# NFC.net
KiCad netlist of a schematic drawn in Altium Designer
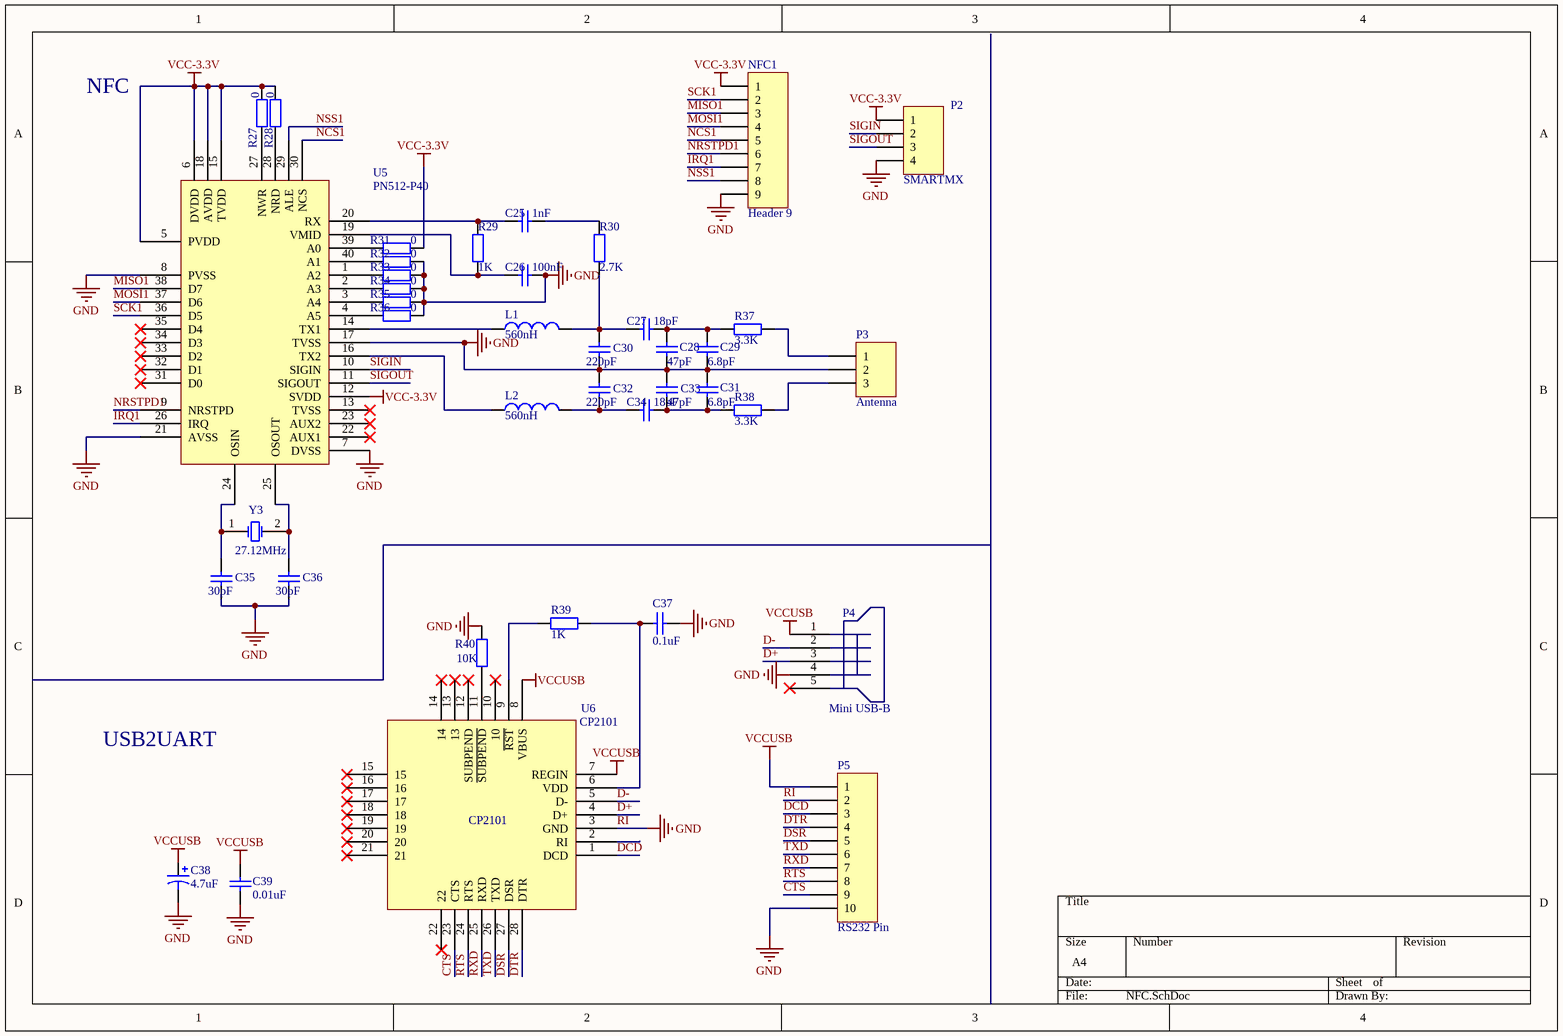
[diagram p0: NFC.SchDoc]

(export (version "E")
  (design (tool "Eeschema 10.0.6"))
  (components
    (comp (ref "C25")
      (value "1nF")
      (footprint "1608[0603]")
      (description "Capacitor")
      (fields (field (name "Comment") "Cap") (field (name "PUBLISHER") "Altium Limited"))
      (libsource (lib "common") (part "Cap"))
    )
    (comp (ref "C26")
      (value "100nF")
      (footprint "1608[0603]")
      (description "Capacitor")
      (fields (field (name "Comment") "Cap") (field (name "PUBLISHER") "Altium Limited"))
      (libsource (lib "common") (part "Cap"))
    )
    (comp (ref "C27")
      (value "18pF")
      (footprint "1608[0603]")
      (description "Capacitor")
      (fields (field (name "Comment") "Cap") (field (name "PUBLISHER") "Altium Limited"))
      (libsource (lib "common") (part "Cap"))
    )
    (comp (ref "C28")
      (value "47pF")
      (footprint "1608[0603]")
      (description "Capacitor")
      (fields (field (name "Comment") "Cap") (field (name "PUBLISHER") "Altium Limited"))
      (libsource (lib "common") (part "Cap"))
    )
    (comp (ref "C29")
      (value "6.8pF")
      (footprint "1608[0603]")
      (description "Capacitor")
      (fields (field (name "Comment") "Cap") (field (name "PUBLISHER") "Altium Limited"))
      (libsource (lib "common") (part "Cap"))
    )
    (comp (ref "C30")
      (value "220pF")
      (footprint "1608[0603]")
      (description "Capacitor")
      (fields (field (name "Comment") "Cap") (field (name "PUBLISHER") "Altium Limited"))
      (libsource (lib "common") (part "Cap"))
    )
    (comp (ref "C31")
      (value "6.8pF")
      (footprint "1608[0603]")
      (description "Capacitor")
      (fields (field (name "Comment") "Cap") (field (name "PUBLISHER") "Altium Limited"))
      (libsource (lib "common") (part "Cap"))
    )
    (comp (ref "C32")
      (value "220pF")
      (footprint "1608[0603]")
      (description "Capacitor")
      (fields (field (name "Comment") "Cap") (field (name "PUBLISHER") "Altium Limited"))
      (libsource (lib "common") (part "Cap"))
    )
    (comp (ref "C33")
      (value "47pF")
      (footprint "1608[0603]")
      (description "Capacitor")
      (fields (field (name "Comment") "Cap") (field (name "PUBLISHER") "Altium Limited"))
      (libsource (lib "common") (part "Cap"))
    )
    (comp (ref "C34")
      (value "18pF")
      (footprint "1608[0603]")
      (description "Capacitor")
      (fields (field (name "Comment") "Cap") (field (name "PUBLISHER") "Altium Limited"))
      (libsource (lib "common") (part "Cap"))
    )
    (comp (ref "C35")
      (value "30pF")
      (footprint "1608[0603]")
      (description "Capacitor")
      (fields (field (name "Comment") "Cap") (field (name "PUBLISHER") "Altium Limited"))
      (libsource (lib "common") (part "Cap"))
    )
    (comp (ref "C36")
      (value "30pF")
      (footprint "1608[0603]")
      (description "Capacitor")
      (fields (field (name "Comment") "Cap") (field (name "PUBLISHER") "Altium Limited"))
      (libsource (lib "common") (part "Cap"))
    )
    (comp (ref "C37")
      (value "0.1uF")
      (footprint "1608[0603]")
      (description "Capacitor")
      (fields (field (name "Comment") "Cap") (field (name "PUBLISHER") "Altium Limited"))
      (libsource (lib "common") (part "Cap"))
    )
    (comp (ref "C38")
      (value "4.7uF")
      (footprint "2012[0805] - POL")
      (description "Polarized Capacitor (Axial)")
      (fields (field (name "Comment") "CAP POL") (field (name "PUBLISHER") "Altium Limited"))
      (libsource (lib "common") (part "CAP POL"))
    )
    (comp (ref "C39")
      (value "0.01uF")
      (footprint "1608[0603]")
      (description "Capacitor")
      (fields (field (name "Comment") "Cap") (field (name "PUBLISHER") "Altium Limited"))
      (libsource (lib "common") (part "Cap"))
    )
    (comp (ref "L1")
      (value "560nH")
      (footprint "0402-A")
      (description "Inductor")
      (fields (field (name "PUBLISHER") "Altium Limited"))
      (libsource (lib "Miscellaneous Devices") (part "Inductor"))
    )
    (comp (ref "L2")
      (value "560nH")
      (footprint "0402-A")
      (description "Inductor")
      (fields (field (name "PUBLISHER") "Altium Limited"))
      (libsource (lib "Miscellaneous Devices") (part "Inductor"))
    )
    (comp (ref "NFC1")
      (value "Header 9")
      (footprint "HDR1X9")
      (description "Header, 9-Pin")
      (fields (field (name "PUBLISHER") "Altium Limited"))
      (libsource (lib "Miscellaneous Connectors") (part "Header 9"))
    )
    (comp (ref "P2")
      (value "SMARTMX")
      (footprint "HDR1X4")
      (description "Header, 4-Pin")
      (fields (field (name "PUBLISHER") "Altium Limited"))
      (libsource (lib "Miscellaneous Connectors") (part "Header 4"))
    )
    (comp (ref "P3")
      (value "Antenna")
      (footprint "HDR1X3")
      (description "Header, 3-Pin")
      (fields (field (name "PUBLISHER") "Altium Limited"))
      (libsource (lib "Miscellaneous Connectors") (part "Header 3"))
    )
    (comp (ref "P4")
      (value "Mini USB-B")
      (footprint "MINI USB-501")
      (description "Mini USB Type B")
      (libsource (lib "USB2UART") (part "USB"))
    )
    (comp (ref "P5")
      (value "RS232 Pin")
      (footprint "HDR1X10")
      (description "Header, 10-Pin")
      (fields (field (name "PUBLISHER") "Altium Limited"))
      (libsource (lib "Miscellaneous Connectors") (part "Header 10"))
    )
    (comp (ref "R27")
      (value "0")
      (footprint "1608[0603]")
      (description "Resistor")
      (fields (field (name "Comment") "RES") (field (name "PUBLISHER") "Altium Limited"))
      (libsource (lib "") (part "RES_1"))
    )
    (comp (ref "R28")
      (value "0")
      (footprint "1608[0603]")
      (description "Resistor")
      (fields (field (name "Comment") "RES") (field (name "PUBLISHER") "Altium Limited"))
      (libsource (lib "") (part "RES_1"))
    )
    (comp (ref "R29")
      (value "1K")
      (footprint "1608[0603]")
      (description "Resistor")
      (fields (field (name "Comment") "RES") (field (name "PUBLISHER") "Altium Limited"))
      (libsource (lib "") (part "RES_1"))
    )
    (comp (ref "R30")
      (value "2.7K")
      (footprint "1608[0603]")
      (description "Resistor")
      (fields (field (name "Comment") "RES") (field (name "PUBLISHER") "Altium Limited"))
      (libsource (lib "") (part "RES_1"))
    )
    (comp (ref "R31")
      (value "0")
      (footprint "1608[0603]")
      (description "Resistor")
      (fields (field (name "Comment") "RES") (field (name "PUBLISHER") "Altium Limited"))
      (libsource (lib "common") (part "RES"))
    )
    (comp (ref "R32")
      (value "0")
      (footprint "1608[0603]")
      (description "Resistor")
      (fields (field (name "Comment") "RES") (field (name "PUBLISHER") "Altium Limited"))
      (libsource (lib "common") (part "RES"))
    )
    (comp (ref "R33")
      (value "0")
      (footprint "1608[0603]")
      (description "Resistor")
      (fields (field (name "Comment") "RES") (field (name "PUBLISHER") "Altium Limited"))
      (libsource (lib "common") (part "RES"))
    )
    (comp (ref "R34")
      (value "0")
      (footprint "1608[0603]")
      (description "Resistor")
      (fields (field (name "Comment") "RES") (field (name "PUBLISHER") "Altium Limited"))
      (libsource (lib "common") (part "RES"))
    )
    (comp (ref "R35")
      (value "0")
      (footprint "1608[0603]")
      (description "Resistor")
      (fields (field (name "Comment") "RES") (field (name "PUBLISHER") "Altium Limited"))
      (libsource (lib "common") (part "RES"))
    )
    (comp (ref "R36")
      (value "0")
      (footprint "1608[0603]")
      (description "Resistor")
      (fields (field (name "Comment") "RES") (field (name "PUBLISHER") "Altium Limited"))
      (libsource (lib "common") (part "RES"))
    )
    (comp (ref "R37")
      (value "3.3K")
      (footprint "1608[0603]")
      (description "Resistor")
      (fields (field (name "Comment") "RES") (field (name "PUBLISHER") "Altium Limited"))
      (libsource (lib "common") (part "RES"))
    )
    (comp (ref "R38")
      (value "3.3K")
      (footprint "1608[0603]")
      (description "Resistor")
      (fields (field (name "Comment") "RES") (field (name "PUBLISHER") "Altium Limited"))
      (libsource (lib "common") (part "RES"))
    )
    (comp (ref "R39")
      (value "1K")
      (footprint "1608[0603]")
      (description "Resistor")
      (fields (field (name "Comment") "Res") (field (name "PUBLISHER") "Altium Limited"))
      (libsource (lib "common") (part "RES"))
    )
    (comp (ref "R40")
      (value "10K")
      (footprint "1608[0603]")
      (description "Resistor")
      (fields (field (name "Comment") "Res") (field (name "PUBLISHER") "Altium Limited"))
      (libsource (lib "") (part "RES_1"))
    )
    (comp (ref "U5")
      (value "PN512-P40")
      (footprint "QFN50P600X600-40VN")
      (libsource (lib "*") (part "PN511-P40"))
    )
    (comp (ref "U6")
      (value "CP2101")
      (footprint "QFN50P500X500-28VAN")
      (libsource (lib "USB2UART") (part "CP2101"))
    )
    (comp (ref "Y3")
      (value "27.12MHz")
      (footprint "XTAL")
      (description "Crystal Oscillator")
      (fields (field (name "PUBLISHER") "Altium Limited"))
      (libsource (lib "common") (part "XTAL"))
    )
  )
  (nets
    (net (code "1") (name "/CTS") (class "Default")
      (node (ref "P5") (pin "9") (pinfunction "9_9") (pintype "passive"))
      (node (ref "U6") (pin "23") (pinfunction "CTS_23") (pintype "passive"))
    )
    (net (code "2") (name "/D+") (class "Default")
      (node (ref "P4") (pin "3") (pinfunction "3_3") (pintype "passive"))
      (node (ref "U6") (pin "4") (pinfunction "D+_4") (pintype "passive"))
    )
    (net (code "3") (name "/D-") (class "Default")
      (node (ref "P4") (pin "2") (pinfunction "2_2") (pintype "passive"))
      (node (ref "U6") (pin "5") (pinfunction "D-_5") (pintype "passive"))
    )
    (net (code "4") (name "/DCD") (class "Default")
      (node (ref "P5") (pin "3") (pinfunction "3_3") (pintype "passive"))
      (node (ref "U6") (pin "1") (pinfunction "DCD_1") (pintype "passive"))
    )
    (net (code "5") (name "/DSR") (class "Default")
      (node (ref "P5") (pin "5") (pinfunction "5_5") (pintype "passive"))
      (node (ref "U6") (pin "27") (pinfunction "DSR_27") (pintype "passive"))
    )
    (net (code "6") (name "/DTR") (class "Default")
      (node (ref "P5") (pin "4") (pinfunction "4_4") (pintype "passive"))
      (node (ref "U6") (pin "28") (pinfunction "DTR_28") (pintype "passive"))
    )
    (net (code "7") (name "/IRQ1") (class "Default")
      (node (ref "NFC1") (pin "7") (pinfunction "7_7") (pintype "passive"))
      (node (ref "U5") (pin "26") (pinfunction "IRQ_26") (pintype "passive"))
    )
    (net (code "8") (name "/MISO1") (class "Default")
      (node (ref "NFC1") (pin "3") (pinfunction "3_3") (pintype "passive"))
      (node (ref "U5") (pin "38") (pinfunction "D7_38") (pintype "passive"))
    )
    (net (code "9") (name "/MOSI1") (class "Default")
      (node (ref "NFC1") (pin "4") (pinfunction "4_4") (pintype "passive"))
      (node (ref "U5") (pin "37") (pinfunction "D6_37") (pintype "passive"))
    )
    (net (code "10") (name "/NCS1") (class "Default")
      (node (ref "NFC1") (pin "5") (pinfunction "5_5") (pintype "passive"))
      (node (ref "U5") (pin "30") (pinfunction "NCS_30") (pintype "passive"))
    )
    (net (code "11") (name "/NRSTPD1") (class "Default")
      (node (ref "NFC1") (pin "6") (pinfunction "6_6") (pintype "passive"))
      (node (ref "U5") (pin "9") (pinfunction "NRSTPD_9") (pintype "passive"))
    )
    (net (code "12") (name "/NSS1") (class "Default")
      (node (ref "NFC1") (pin "8") (pinfunction "8_8") (pintype "passive"))
      (node (ref "U5") (pin "29") (pinfunction "ALE_29") (pintype "passive"))
    )
    (net (code "13") (name "/RTS") (class "Default")
      (node (ref "P5") (pin "8") (pinfunction "8_8") (pintype "passive"))
      (node (ref "U6") (pin "24") (pinfunction "RTS_24") (pintype "passive"))
    )
    (net (code "14") (name "/RXD") (class "Default")
      (node (ref "P5") (pin "7") (pinfunction "7_7") (pintype "passive"))
      (node (ref "U6") (pin "25") (pinfunction "RXD_25") (pintype "passive"))
    )
    (net (code "15") (name "/SCK1") (class "Default")
      (node (ref "NFC1") (pin "2") (pinfunction "2_2") (pintype "passive"))
      (node (ref "U5") (pin "36") (pinfunction "D5_36") (pintype "passive"))
    )
    (net (code "16") (name "/SIGIN") (class "Default")
      (node (ref "P2") (pin "2") (pinfunction "2_2") (pintype "passive"))
      (node (ref "U5") (pin "10") (pinfunction "SIGIN_10") (pintype "passive"))
    )
    (net (code "17") (name "/SIGOUT") (class "Default")
      (node (ref "P2") (pin "3") (pinfunction "3_3") (pintype "passive"))
      (node (ref "U5") (pin "11") (pinfunction "SIGOUT_11") (pintype "passive"))
    )
    (net (code "18") (name "/TXD") (class "Default")
      (node (ref "P5") (pin "6") (pinfunction "6_6") (pintype "passive"))
      (node (ref "U6") (pin "26") (pinfunction "TXD_26") (pintype "passive"))
    )
    (net (code "19") (name "GND") (class "Default")
      (node (ref "C26") (pin "2") (pinfunction "2_2") (pintype "passive"))
      (node (ref "C28") (pin "1") (pinfunction "1_1") (pintype "passive"))
      (node (ref "C29") (pin "1") (pinfunction "1_1") (pintype "passive"))
      (node (ref "C30") (pin "1") (pinfunction "1_1") (pintype "passive"))
      (node (ref "C31") (pin "2") (pinfunction "2_2") (pintype "passive"))
      (node (ref "C32") (pin "2") (pinfunction "2_2") (pintype "passive"))
      (node (ref "C33") (pin "2") (pinfunction "2_2") (pintype "passive"))
      (node (ref "C35") (pin "1") (pinfunction "1_1") (pintype "passive"))
      (node (ref "C36") (pin "1") (pinfunction "1_1") (pintype "passive"))
      (node (ref "C37") (pin "1") (pinfunction "1_1") (pintype "passive"))
      (node (ref "C38") (pin "2") (pinfunction "2_2") (pintype "passive"))
      (node (ref "C39") (pin "1") (pinfunction "1_1") (pintype "passive"))
      (node (ref "NFC1") (pin "9") (pinfunction "9_9") (pintype "passive"))
      (node (ref "P2") (pin "4") (pinfunction "4_4") (pintype "passive"))
      (node (ref "P3") (pin "2") (pinfunction "2_2") (pintype "passive"))
      (node (ref "P4") (pin "4") (pinfunction "4_4") (pintype "passive"))
      (node (ref "P5") (pin "10") (pinfunction "10_10") (pintype "passive"))
      (node (ref "P5") (pin "2") (pinfunction "2_2") (pintype "passive"))
      (node (ref "R32") (pin "1") (pinfunction "1_1") (pintype "passive"))
      (node (ref "R33") (pin "1") (pinfunction "1_1") (pintype "passive"))
      (node (ref "R34") (pin "1") (pinfunction "1_1") (pintype "passive"))
      (node (ref "R35") (pin "1") (pinfunction "1_1") (pintype "passive"))
      (node (ref "R36") (pin "1") (pinfunction "1_1") (pintype "passive"))
      (node (ref "R40") (pin "2") (pinfunction "2_2") (pintype "passive"))
      (node (ref "U5") (pin "17") (pinfunction "TVSS_17") (pintype "passive"))
      (node (ref "U5") (pin "21") (pinfunction "AVSS_21") (pintype "passive"))
      (node (ref "U5") (pin "7") (pinfunction "DVSS_7") (pintype "passive"))
      (node (ref "U5") (pin "8") (pinfunction "PVSS_8") (pintype "passive"))
      (node (ref "U6") (pin "3") (pinfunction "GND_3") (pintype "passive"))
    )
    (net (code "20") (name "Net-(C25-Pad2)") (class "Default")
      (node (ref "C25") (pin "2") (pinfunction "2_2") (pintype "passive"))
      (node (ref "R30") (pin "2") (pinfunction "2_2") (pintype "passive"))
    )
    (net (code "21") (name "Net-(C27-Pad1)") (class "Default")
      (node (ref "C27") (pin "1") (pinfunction "1_1") (pintype "passive"))
      (node (ref "C30") (pin "2") (pinfunction "2_2") (pintype "passive"))
      (node (ref "L1") (pin "2") (pinfunction "2_2") (pintype "passive"))
      (node (ref "R30") (pin "1") (pinfunction "1_1") (pintype "passive"))
    )
    (net (code "22") (name "Net-(C27-Pad2)") (class "Default")
      (node (ref "C27") (pin "2") (pinfunction "2_2") (pintype "passive"))
      (node (ref "C28") (pin "2") (pinfunction "2_2") (pintype "passive"))
      (node (ref "C29") (pin "2") (pinfunction "2_2") (pintype "passive"))
      (node (ref "R37") (pin "2") (pinfunction "2_2") (pintype "passive"))
    )
    (net (code "23") (name "Net-(C31-Pad1)") (class "Default")
      (node (ref "C31") (pin "1") (pinfunction "1_1") (pintype "passive"))
      (node (ref "C33") (pin "1") (pinfunction "1_1") (pintype "passive"))
      (node (ref "C34") (pin "2") (pinfunction "2_2") (pintype "passive"))
      (node (ref "R38") (pin "2") (pinfunction "2_2") (pintype "passive"))
    )
    (net (code "24") (name "Net-(C32-Pad1)") (class "Default")
      (node (ref "C32") (pin "1") (pinfunction "1_1") (pintype "passive"))
      (node (ref "C34") (pin "1") (pinfunction "1_1") (pintype "passive"))
      (node (ref "L2") (pin "2") (pinfunction "2_2") (pintype "passive"))
    )
    (net (code "25") (name "Net-(P3-Pad1)") (class "Default")
      (node (ref "P3") (pin "1") (pinfunction "1_1") (pintype "passive"))
      (node (ref "R37") (pin "1") (pinfunction "1_1") (pintype "passive"))
    )
    (net (code "26") (name "Net-(P3-Pad3)") (class "Default")
      (node (ref "P3") (pin "3") (pinfunction "3_3") (pintype "passive"))
      (node (ref "R38") (pin "1") (pinfunction "1_1") (pintype "passive"))
    )
    (net (code "27") (name "Net-(U5-A0)") (class "Default")
      (node (ref "R31") (pin "2") (pinfunction "2_2") (pintype "passive"))
      (node (ref "U5") (pin "39") (pinfunction "A0_39") (pintype "passive"))
    )
    (net (code "28") (name "Net-(U5-A1)") (class "Default")
      (node (ref "R32") (pin "2") (pinfunction "2_2") (pintype "passive"))
      (node (ref "U5") (pin "40") (pinfunction "A1_40") (pintype "passive"))
    )
    (net (code "29") (name "Net-(U5-A2)") (class "Default")
      (node (ref "R33") (pin "2") (pinfunction "2_2") (pintype "passive"))
      (node (ref "U5") (pin "1") (pinfunction "A2_1") (pintype "passive"))
    )
    (net (code "30") (name "Net-(U5-A3)") (class "Default")
      (node (ref "R34") (pin "2") (pinfunction "2_2") (pintype "passive"))
      (node (ref "U5") (pin "2") (pinfunction "A3_2") (pintype "passive"))
    )
    (net (code "31") (name "Net-(U5-A4)") (class "Default")
      (node (ref "R35") (pin "2") (pinfunction "2_2") (pintype "passive"))
      (node (ref "U5") (pin "3") (pinfunction "A4_3") (pintype "passive"))
    )
    (net (code "32") (name "Net-(U5-A5)") (class "Default")
      (node (ref "R36") (pin "2") (pinfunction "2_2") (pintype "passive"))
      (node (ref "U5") (pin "4") (pinfunction "A5_4") (pintype "passive"))
    )
    (net (code "33") (name "Net-(U5-NRD)") (class "Default")
      (node (ref "R28") (pin "1") (pinfunction "1_1") (pintype "passive"))
      (node (ref "U5") (pin "28") (pinfunction "NRD_28") (pintype "passive"))
    )
    (net (code "34") (name "Net-(U5-NWR)") (class "Default")
      (node (ref "R27") (pin "1") (pinfunction "1_1") (pintype "passive"))
      (node (ref "U5") (pin "27") (pinfunction "NWR_27") (pintype "passive"))
    )
    (net (code "35") (name "Net-(U5-OSIN)") (class "Default")
      (node (ref "C35") (pin "2") (pinfunction "2_2") (pintype "passive"))
      (node (ref "U5") (pin "24") (pinfunction "OSIN_24") (pintype "passive"))
      (node (ref "Y3") (pin "1") (pinfunction "OSC1_1") (pintype "passive"))
    )
    (net (code "36") (name "Net-(U5-OSOUT)") (class "Default")
      (node (ref "C36") (pin "2") (pinfunction "2_2") (pintype "passive"))
      (node (ref "U5") (pin "25") (pinfunction "OSOUT_25") (pintype "passive"))
      (node (ref "Y3") (pin "2") (pinfunction "OSC2_2") (pintype "passive"))
    )
    (net (code "37") (name "Net-(U5-RX)") (class "Default")
      (node (ref "C25") (pin "1") (pinfunction "1_1") (pintype "passive"))
      (node (ref "R29") (pin "2") (pinfunction "2_2") (pintype "passive"))
      (node (ref "U5") (pin "20") (pinfunction "RX_20") (pintype "passive"))
    )
    (net (code "38") (name "Net-(U5-TX1)") (class "Default")
      (node (ref "L1") (pin "1") (pinfunction "1_1") (pintype "passive"))
      (node (ref "U5") (pin "14") (pinfunction "TX1_14") (pintype "passive"))
    )
    (net (code "39") (name "Net-(U5-TX2)") (class "Default")
      (node (ref "L2") (pin "1") (pinfunction "1_1") (pintype "passive"))
      (node (ref "U5") (pin "16") (pinfunction "TX2_16") (pintype "passive"))
    )
    (net (code "40") (name "Net-(U5-VMID)") (class "Default")
      (node (ref "C26") (pin "1") (pinfunction "1_1") (pintype "passive"))
      (node (ref "R29") (pin "1") (pinfunction "1_1") (pintype "passive"))
      (node (ref "U5") (pin "19") (pinfunction "VMID_19") (pintype "passive"))
    )
    (net (code "41") (name "Net-(U6-VDD)") (class "Default")
      (node (ref "C37") (pin "2") (pinfunction "2_2") (pintype "passive"))
      (node (ref "R39") (pin "1") (pinfunction "1_1") (pintype "passive"))
      (node (ref "U6") (pin "6") (pinfunction "VDD_6") (pintype "passive"))
    )
    (net (code "42") (name "Net-(U6-~{RST})") (class "Default")
      (node (ref "R39") (pin "2") (pinfunction "2_2") (pintype "passive"))
      (node (ref "U6") (pin "9") (pinfunction "~{RST}_9") (pintype "passive"))
    )
    (net (code "43") (name "Net-(U6-~{SUBPEND})") (class "Default")
      (node (ref "R40") (pin "1") (pinfunction "1_1") (pintype "passive"))
      (node (ref "U6") (pin "11") (pinfunction "~{SUBPEND}_11") (pintype "passive"))
    )
    (net (code "44") (name "VCC-3.3V") (class "Default")
      (node (ref "NFC1") (pin "1") (pinfunction "1_1") (pintype "passive"))
      (node (ref "P2") (pin "1") (pinfunction "1_1") (pintype "passive"))
      (node (ref "R27") (pin "2") (pinfunction "2_2") (pintype "passive"))
      (node (ref "R28") (pin "2") (pinfunction "2_2") (pintype "passive"))
      (node (ref "R31") (pin "1") (pinfunction "1_1") (pintype "passive"))
      (node (ref "U5") (pin "12") (pinfunction "SVDD_12") (pintype "passive"))
      (node (ref "U5") (pin "15") (pinfunction "TVDD_15") (pintype "passive"))
      (node (ref "U5") (pin "18") (pinfunction "AVDD_18") (pintype "passive"))
      (node (ref "U5") (pin "5") (pinfunction "PVDD_5") (pintype "passive"))
      (node (ref "U5") (pin "6") (pinfunction "DVDD_6") (pintype "passive"))
    )
    (net (code "45") (name "VCCUSB") (class "Default")
      (node (ref "C38") (pin "1") (pinfunction "1_1") (pintype "passive"))
      (node (ref "C39") (pin "2") (pinfunction "2_2") (pintype "passive"))
      (node (ref "P4") (pin "1") (pinfunction "1_1") (pintype "passive"))
      (node (ref "P5") (pin "1") (pinfunction "1_1") (pintype "passive"))
      (node (ref "U6") (pin "7") (pinfunction "REGIN_7") (pintype "passive"))
      (node (ref "U6") (pin "8") (pinfunction "VBUS_8") (pintype "passive"))
    )
    (net (code "46") (name "unconnected-(P4-Pad5)") (class "Default")
      (node (ref "P4") (pin "5") (pinfunction "5_5") (pintype "passive+no_connect"))
    )
    (net (code "47") (name "unconnected-(U5-AUX1-Pad22)") (class "Default")
      (node (ref "U5") (pin "22") (pinfunction "AUX1_22") (pintype "passive+no_connect"))
    )
    (net (code "48") (name "unconnected-(U5-AUX2-Pad23)") (class "Default")
      (node (ref "U5") (pin "23") (pinfunction "AUX2_23") (pintype "passive+no_connect"))
    )
    (net (code "49") (name "unconnected-(U5-D0-Pad31)") (class "Default")
      (node (ref "U5") (pin "31") (pinfunction "D0_31") (pintype "passive+no_connect"))
    )
    (net (code "50") (name "unconnected-(U5-D1-Pad32)") (class "Default")
      (node (ref "U5") (pin "32") (pinfunction "D1_32") (pintype "passive+no_connect"))
    )
    (net (code "51") (name "unconnected-(U5-D2-Pad33)") (class "Default")
      (node (ref "U5") (pin "33") (pinfunction "D2_33") (pintype "passive+no_connect"))
    )
    (net (code "52") (name "unconnected-(U5-D3-Pad34)") (class "Default")
      (node (ref "U5") (pin "34") (pinfunction "D3_34") (pintype "passive+no_connect"))
    )
    (net (code "53") (name "unconnected-(U5-D4-Pad35)") (class "Default")
      (node (ref "U5") (pin "35") (pinfunction "D4_35") (pintype "passive+no_connect"))
    )
    (net (code "54") (name "unconnected-(U5-TVSS-Pad13)") (class "Default")
      (node (ref "U5") (pin "13") (pinfunction "TVSS_13") (pintype "passive+no_connect"))
    )
    (net (code "55") (name "unconnected-(U6-Pad10)") (class "Default")
      (node (ref "U6") (pin "10") (pinfunction "10_10") (pintype "passive+no_connect"))
    )
    (net (code "56") (name "unconnected-(U6-Pad13)") (class "Default")
      (node (ref "U6") (pin "13") (pinfunction "13_13") (pintype "passive+no_connect"))
    )
    (net (code "57") (name "unconnected-(U6-Pad14)") (class "Default")
      (node (ref "U6") (pin "14") (pinfunction "14_14") (pintype "passive+no_connect"))
    )
    (net (code "58") (name "unconnected-(U6-Pad15)") (class "Default")
      (node (ref "U6") (pin "15") (pinfunction "15_15") (pintype "passive+no_connect"))
    )
    (net (code "59") (name "unconnected-(U6-Pad16)") (class "Default")
      (node (ref "U6") (pin "16") (pinfunction "16_16") (pintype "passive+no_connect"))
    )
    (net (code "60") (name "unconnected-(U6-Pad17)") (class "Default")
      (node (ref "U6") (pin "17") (pinfunction "17_17") (pintype "passive+no_connect"))
    )
    (net (code "61") (name "unconnected-(U6-Pad18)") (class "Default")
      (node (ref "U6") (pin "18") (pinfunction "18_18") (pintype "passive+no_connect"))
    )
    (net (code "62") (name "unconnected-(U6-Pad19)") (class "Default")
      (node (ref "U6") (pin "19") (pinfunction "19_19") (pintype "passive+no_connect"))
    )
    (net (code "63") (name "unconnected-(U6-Pad20)") (class "Default")
      (node (ref "U6") (pin "20") (pinfunction "20_20") (pintype "passive+no_connect"))
    )
    (net (code "64") (name "unconnected-(U6-Pad21)") (class "Default")
      (node (ref "U6") (pin "21") (pinfunction "21_21") (pintype "passive+no_connect"))
    )
    (net (code "65") (name "unconnected-(U6-Pad22)") (class "Default")
      (node (ref "U6") (pin "22") (pinfunction "22_22") (pintype "passive+no_connect"))
    )
    (net (code "66") (name "unconnected-(U6-RI-Pad2)") (class "Default")
      (node (ref "U6") (pin "2") (pinfunction "RI_2") (pintype "passive"))
    )
    (net (code "67") (name "unconnected-(U6-SUBPEND-Pad12)") (class "Default")
      (node (ref "U6") (pin "12") (pinfunction "SUBPEND_12") (pintype "passive+no_connect"))
    )
  )
)
